# Rechargeable_Circuit.net
KiCad netlist of a schematic drawn in Altium Designer
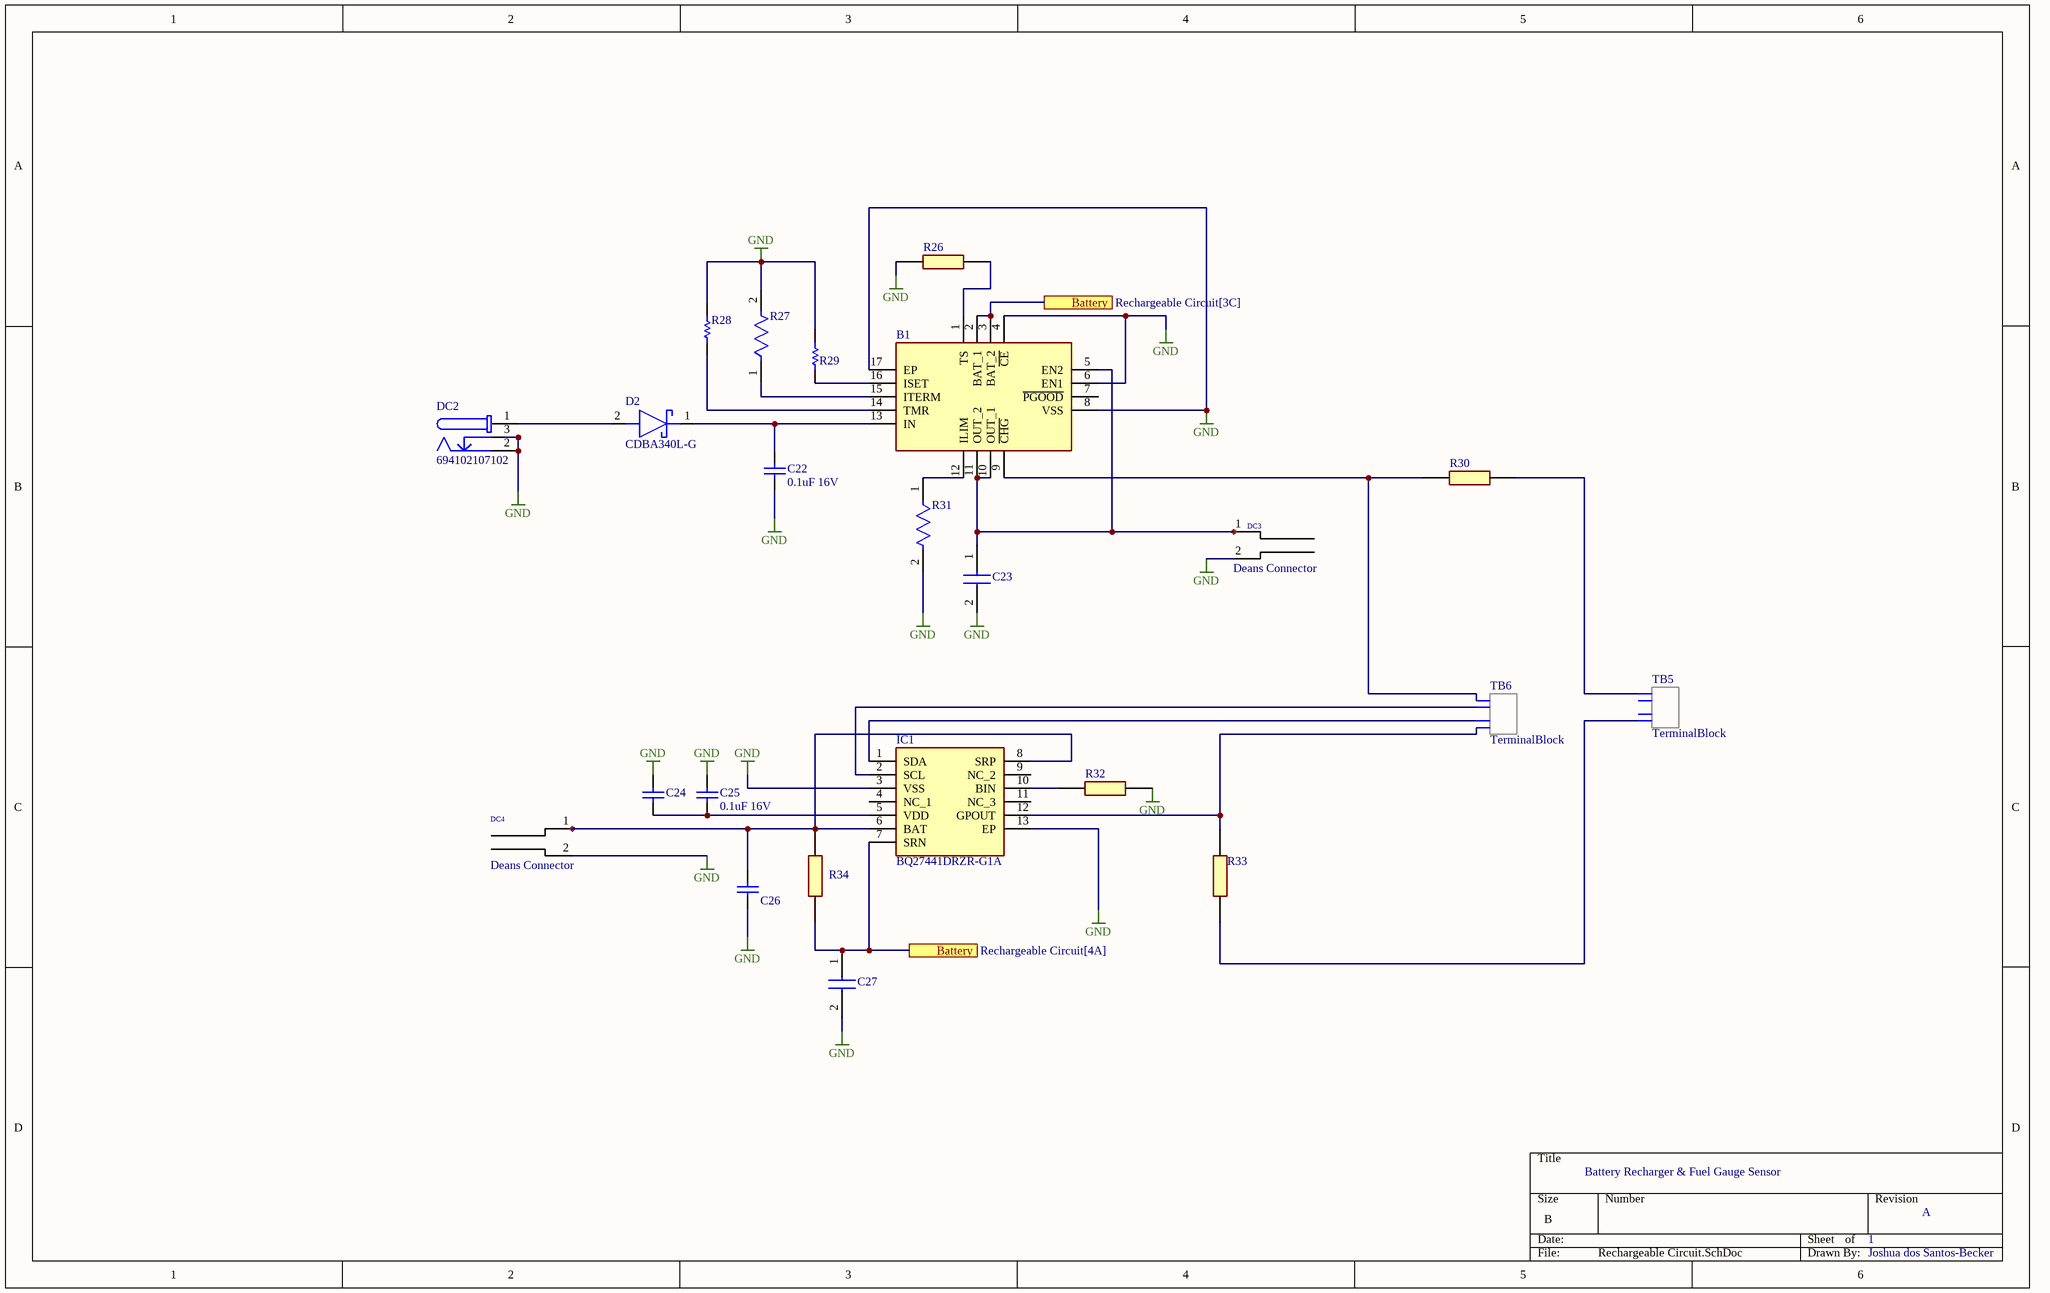
[diagram p0: Rechargeable Circuit.SchDoc]

(export (version "E")
  (design (tool "Eeschema 10.0.6"))
  (components
    (comp (ref "B1")
      (value "BQ24232HRGTR")
      (footprint "QFN50P300X300X100-17N-D")
      (description "USB-Friendly Lithium Based Battery Charger With Power-Path For 4.35V Batteries")
      (fields (field (name "MOUSER PART NUMBER") "595-BQ24232HRGTR"))
      (libsource (lib "gsl") (part "BQ24232HRGTR"))
    )
    (comp (ref "C22")
      (value "0.1uF 16V")
      (footprint "CAPC2113X100X50ML30T10")
      (description "C0805X104K4RACTU")
      (fields (field (name "MANUFACTURER") "Kemet"))
      (libsource (lib "Altium Content Vault") (part "CAP"))
    )
    (comp (ref "C23")
      (value "GRM32DR71C106KA01L")
      (footprint "gfl:GRM32DR61C106KA01L")
      (description "Capacitor")
      (fields (field (name "MOUSER PART NUMBER") "81-GRM32R71C106KA01L"))
      (libsource (lib "*") (part "GRM32DR71C106KA01L"))
    )
    (comp (ref "C24")
      (value "C1206C105K3RACTU")
      (footprint "CAPC3216X180X50ML20T25")
      (description "Chip Capacitor, 1 uF, +/- 10%, 25 V, -55 to 125 degC, 1206 (3216 Metric), RoHS, Tape and Reel")
      (fields (field (name "MANUFACTURER") "Kemet") (field (name "TOLERANCE") "10%"))
      (libsource (lib "Altium Content Vault") (part "CAP-NP-2"))
    )
    (comp (ref "C25")
      (value "0.1uF 16V")
      (footprint "CAPC2113X100X50ML30T10")
      (description "C0805X104K4RACTU")
      (fields (field (name "MANUFACTURER") "Kemet"))
      (libsource (lib "Altium Content Vault") (part "CAP"))
    )
    (comp (ref "C26")
      (value "C1206C105K3RACTU")
      (footprint "CAPC3216X180X50ML20T25")
      (description "Chip Capacitor, 1 uF, +/- 10%, 25 V, -55 to 125 degC, 1206 (3216 Metric), RoHS, Tape and Reel")
      (fields (field (name "MANUFACTURER") "Kemet") (field (name "TOLERANCE") "10%"))
      (libsource (lib "Altium Content Vault") (part "CAP-NP-2"))
    )
    (comp (ref "C27")
      (value "GRM32DR71C106KA01L")
      (footprint "gfl:GRM32DR61C106KA01L")
      (description "Capacitor")
      (fields (field (name "MOUSER PART NUMBER") "81-GRM32R71C106KA01L"))
      (libsource (lib "*") (part "GRM32DR71C106KA01L"))
    )
    (comp (ref "D2")
      (value "CDBA340L-G")
      (footprint "DIONM5127X229N")
      (description "Schottky Diode")
      (fields (field (name "MOUSER PART NUMBER") "750-CDBA340L-G"))
      (libsource (lib "gsl") (part "CDBA340L-G"))
    )
    (comp (ref "DC2")
      (value "694102107102")
      (footprint "694102107102")
      (libsource (lib "gsl") (part "DC Power Jack"))
    )
    (comp (ref "DC3")
      (value "Deans Connector")
      (footprint "Deans")
      (libsource (lib "gsl") (part "Deans Connector"))
    )
    (comp (ref "DC4")
      (value "Deans Connector")
      (footprint "Deans")
      (libsource (lib "gsl") (part "Deans Connector"))
    )
    (comp (ref "IC1")
      (value "BQ27441DRZR-G1A")
      (footprint "gfl:BQ27441DRZRG1A")
      (description "Integrated Circuit")
      (fields (field (name "MOUSER PART NUMBER") "595-BQ27441DRZR-G1A"))
      (libsource (lib "gsl") (part "BQ27441DRZR-G1A"))
    )
    (comp (ref "R26")
      (value "CRM2512QJW-103ELF")
      (footprint "RESC6331X80N")
      (description "ResPowerQ 2512 10k 5% 2W TC200")
      (fields (field (name "MOUSER PART NUMBER") "652-CRM2512QJW-103E"))
      (libsource (lib "gsl") (part "CRM2512QJW-103ELF"))
    )
    (comp (ref "R27")
      (value "RG2012V-1431-B-T5")
      (footprint "FP-RG2012-MFG")
      (description "Automotive Metal Thin Film Chip Resistor, 0805, 1.43kΩ, 0.1%, 5ppm/°C, 0.125W, 150V")
      (fields (field (name "TOLERANCE") "0.1%"))
      (libsource (lib "Altium Content Vault") (part "1029c3af85768c4190bb7ad29bc67b5"))
    )
    (comp (ref "R28")
      (value "CRCW120656K2FKEA")
      (footprint "RESC3216X60X45ML10T20")
      (fields (field (name "MANUFACTURER") "Vishay Dale"))
      (libsource (lib "Altium Content Vault") (part "RES"))
    )
    (comp (ref "R29")
      (value "1K74 1% 2010(5025)")
      (footprint "RESC2010(5025)_L")
      (description "1K74 0.75W 1% 2010 (5025 Metric)  SMD")
      (fields (field (name "POWER") "0.75 W") (field (name "TOLERANCE") "1 %"))
      (libsource (lib "Altium Content Vault") (part "RES"))
    )
    (comp (ref "R30")
      (value "CRM2512QJW-103ELF")
      (footprint "RESC6331X80N")
      (description "ResPowerQ 2512 10k 5% 2W TC200")
      (fields (field (name "MOUSER PART NUMBER") "652-CRM2512QJW-103E"))
      (libsource (lib "gsl") (part "CRM2512QJW-103ELF"))
    )
    (comp (ref "R31")
      (value "CRCW08053K09FKEA")
      (footprint "FP-CRCW0805-e3-IPC_C")
      (description "RES Thick Film, 3.09kΩ, 1%, 0.125W, 100ppm/°C, 0805")
      (fields (field (name "TOLERANCE") "1%"))
      (libsource (lib "Altium Content Vault") (part "1029c3af85768c4190bb7ad29bc67b5"))
    )
    (comp (ref "R32")
      (value "CRM2512QJW-103ELF")
      (footprint "RESC6331X80N")
      (description "ResPowerQ 2512 10k 5% 2W TC200")
      (fields (field (name "MOUSER PART NUMBER") "652-CRM2512QJW-103E"))
      (libsource (lib "gsl") (part "CRM2512QJW-103ELF"))
    )
    (comp (ref "R33")
      (value "CRM2512QJW-103ELF")
      (footprint "RESC6331X80N")
      (description "ResPowerQ 2512 10k 5% 2W TC200")
      (fields (field (name "MOUSER PART NUMBER") "652-CRM2512QJW-103E"))
      (libsource (lib "") (part "CRM2512QJW-103ELF_2"))
    )
    (comp (ref "R34")
      (value "CRM2512QJW-103ELF")
      (footprint "RESC6331X80N")
      (description "ResPowerQ 2512 10k 5% 2W TC200")
      (fields (field (name "MOUSER PART NUMBER") "652-CRM2512QJW-103E"))
      (libsource (lib "") (part "CRM2512QJW-103ELF_1"))
    )
    (comp (ref "TB5")
      (value "TerminalBlock")
      (footprint "PHOENIX_1725672")
      (libsource (lib "gsl") (part "TerminalBlock"))
    )
    (comp (ref "TB6")
      (value "TerminalBlock")
      (footprint "PHOENIX_1725672")
      (libsource (lib "gsl") (part "TerminalBlock"))
    )
  )
  (nets
    (net (code "1") (name "/Battery") (class "Default")
      (node (ref "B1") (pin "2") (pinfunction "BAT_1_2") (pintype "passive"))
      (node (ref "B1") (pin "3") (pinfunction "BAT_2_3") (pintype "passive"))
      (node (ref "C27") (pin "1") (pinfunction "1_1") (pintype "passive"))
      (node (ref "IC1") (pin "7") (pinfunction "SRN_7") (pintype "passive"))
      (node (ref "R34") (pin "1") (pinfunction "1_1") (pintype "passive"))
    )
    (net (code "2") (name "GND") (class "Default")
      (node (ref "B1") (pin "17") (pinfunction "EP_17") (pintype "passive"))
      (node (ref "B1") (pin "4") (pinfunction "~{CE}_4") (pintype "passive"))
      (node (ref "B1") (pin "6") (pinfunction "EN1_6") (pintype "passive"))
      (node (ref "B1") (pin "8") (pinfunction "VSS_8") (pintype "passive"))
      (node (ref "C22") (pin "2") (pinfunction "2_2") (pintype "passive"))
      (node (ref "C23") (pin "2") (pinfunction "2_2") (pintype "passive"))
      (node (ref "C24") (pin "1") (pinfunction "1_1") (pintype "passive"))
      (node (ref "C25") (pin "1") (pinfunction "1_1") (pintype "passive"))
      (node (ref "C26") (pin "1") (pinfunction "1_1") (pintype "passive"))
      (node (ref "C27") (pin "2") (pinfunction "2_2") (pintype "passive"))
      (node (ref "DC2") (pin "2") (pinfunction "2_2") (pintype "passive"))
      (node (ref "DC2") (pin "3") (pinfunction "3_3") (pintype "passive"))
      (node (ref "DC3") (pin "2") (pinfunction "2_2") (pintype "passive"))
      (node (ref "DC4") (pin "2") (pinfunction "2_2") (pintype "passive"))
      (node (ref "IC1") (pin "13") (pinfunction "EP_13") (pintype "passive"))
      (node (ref "IC1") (pin "3") (pinfunction "VSS_3") (pintype "passive"))
      (node (ref "R26") (pin "1") (pinfunction "1_1") (pintype "passive"))
      (node (ref "R27") (pin "2") (pinfunction "2_2") (pintype "passive"))
      (node (ref "R28") (pin "1") (pinfunction "1_1") (pintype "passive"))
      (node (ref "R29") (pin "2") (pinfunction "2_2") (pintype "passive"))
      (node (ref "R31") (pin "2") (pinfunction "2_2") (pintype "passive"))
      (node (ref "R32") (pin "2") (pinfunction "2_2") (pintype "passive"))
    )
    (net (code "3") (name "Net-(B1-EN2)") (class "Default")
      (node (ref "B1") (pin "10") (pinfunction "OUT_1_10") (pintype "passive"))
      (node (ref "B1") (pin "11") (pinfunction "OUT_2_11") (pintype "passive"))
      (node (ref "B1") (pin "5") (pinfunction "EN2_5") (pintype "passive"))
      (node (ref "C23") (pin "1") (pinfunction "1_1") (pintype "passive"))
      (node (ref "DC3") (pin "1") (pinfunction "1_1") (pintype "passive"))
    )
    (net (code "4") (name "Net-(B1-ILIM)") (class "Default")
      (node (ref "B1") (pin "12") (pinfunction "ILIM_12") (pintype "passive"))
      (node (ref "R31") (pin "1") (pinfunction "1_1") (pintype "passive"))
    )
    (net (code "5") (name "Net-(B1-IN)") (class "Default")
      (node (ref "B1") (pin "13") (pinfunction "IN_13") (pintype "passive"))
      (node (ref "C22") (pin "1") (pinfunction "1_1") (pintype "passive"))
      (node (ref "D2") (pin "1") (pinfunction "K_1") (pintype "passive"))
    )
    (net (code "6") (name "Net-(B1-ISET)") (class "Default")
      (node (ref "B1") (pin "16") (pinfunction "ISET_16") (pintype "passive"))
      (node (ref "R29") (pin "1") (pinfunction "1_1") (pintype "passive"))
    )
    (net (code "7") (name "Net-(B1-ITERM)") (class "Default")
      (node (ref "B1") (pin "15") (pinfunction "ITERM_15") (pintype "passive"))
      (node (ref "R27") (pin "1") (pinfunction "1_1") (pintype "passive"))
    )
    (net (code "8") (name "Net-(B1-TMR)") (class "Default")
      (node (ref "B1") (pin "14") (pinfunction "TMR_14") (pintype "passive"))
      (node (ref "R28") (pin "2") (pinfunction "2_2") (pintype "passive"))
    )
    (net (code "9") (name "Net-(B1-TS)") (class "Default")
      (node (ref "B1") (pin "1") (pinfunction "TS_1") (pintype "passive"))
      (node (ref "R26") (pin "2") (pinfunction "2_2") (pintype "passive"))
    )
    (net (code "10") (name "Net-(B1-~{CHG})") (class "Default")
      (node (ref "B1") (pin "9") (pinfunction "~{CHG}_9") (pintype "passive"))
      (node (ref "R30") (pin "1") (pinfunction "1_1") (pintype "passive"))
      (node (ref "TB6") (pin "1") (pinfunction "1_1") (pintype "passive"))
    )
    (net (code "11") (name "Net-(D2-A)") (class "Default")
      (node (ref "D2") (pin "2") (pinfunction "A_2") (pintype "passive"))
      (node (ref "DC2") (pin "1") (pinfunction "1_1") (pintype "passive"))
    )
    (net (code "12") (name "Net-(IC1-BAT)") (class "Default")
      (node (ref "C26") (pin "2") (pinfunction "2_2") (pintype "passive"))
      (node (ref "DC4") (pin "1") (pinfunction "1_1") (pintype "passive"))
      (node (ref "IC1") (pin "6") (pinfunction "BAT_6") (pintype "passive"))
      (node (ref "IC1") (pin "8") (pinfunction "SRP_8") (pintype "passive"))
      (node (ref "R34") (pin "2") (pinfunction "2_2") (pintype "passive"))
    )
    (net (code "13") (name "Net-(IC1-BIN)") (class "Default")
      (node (ref "IC1") (pin "10") (pinfunction "BIN_10") (pintype "passive"))
      (node (ref "R32") (pin "1") (pinfunction "1_1") (pintype "passive"))
    )
    (net (code "14") (name "Net-(IC1-GPOUT)") (class "Default")
      (node (ref "IC1") (pin "12") (pinfunction "GPOUT_12") (pintype "passive"))
      (node (ref "R33") (pin "1") (pinfunction "1_1") (pintype "passive"))
      (node (ref "TB6") (pin "4") (pinfunction "4_4") (pintype "passive"))
    )
    (net (code "15") (name "Net-(IC1-SCL)") (class "Default")
      (node (ref "IC1") (pin "2") (pinfunction "SCL_2") (pintype "passive"))
      (node (ref "TB6") (pin "2") (pinfunction "2_2") (pintype "passive"))
    )
    (net (code "16") (name "Net-(IC1-SDA)") (class "Default")
      (node (ref "IC1") (pin "1") (pinfunction "SDA_1") (pintype "passive"))
      (node (ref "TB6") (pin "3") (pinfunction "3_3") (pintype "passive"))
    )
    (net (code "17") (name "Net-(IC1-VDD)") (class "Default")
      (node (ref "C24") (pin "2") (pinfunction "2_2") (pintype "passive"))
      (node (ref "C25") (pin "2") (pinfunction "2_2") (pintype "passive"))
      (node (ref "IC1") (pin "5") (pinfunction "VDD_5") (pintype "passive"))
    )
    (net (code "18") (name "Net-(R30-Pad2)") (class "Default")
      (node (ref "R30") (pin "2") (pinfunction "2_2") (pintype "passive"))
      (node (ref "TB5") (pin "1") (pinfunction "1_1") (pintype "passive"))
    )
    (net (code "19") (name "Net-(R33-Pad2)") (class "Default")
      (node (ref "R33") (pin "2") (pinfunction "2_2") (pintype "passive"))
      (node (ref "TB5") (pin "4") (pinfunction "4_4") (pintype "passive"))
    )
    (net (code "20") (name "unconnected-(B1-~{PGOOD}-Pad7)") (class "Default")
      (node (ref "B1") (pin "7") (pinfunction "~{PGOOD}_7") (pintype "passive"))
    )
    (net (code "21") (name "unconnected-(IC1-NC_1-Pad4)") (class "Default")
      (node (ref "IC1") (pin "4") (pinfunction "NC_1_4") (pintype "passive"))
    )
    (net (code "22") (name "unconnected-(IC1-NC_2-Pad9)") (class "Default")
      (node (ref "IC1") (pin "9") (pinfunction "NC_2_9") (pintype "passive"))
    )
    (net (code "23") (name "unconnected-(IC1-NC_3-Pad11)") (class "Default")
      (node (ref "IC1") (pin "11") (pinfunction "NC_3_11") (pintype "passive"))
    )
    (net (code "24") (name "unconnected-(TB5-Pad2)") (class "Default")
      (node (ref "TB5") (pin "2") (pinfunction "2_2") (pintype "passive"))
    )
    (net (code "25") (name "unconnected-(TB5-Pad3)") (class "Default")
      (node (ref "TB5") (pin "3") (pinfunction "3_3") (pintype "passive"))
    )
  )
)
